# circuitPendulum4TIA00.net
KiCad netlist of a schematic drawn in EAGLE
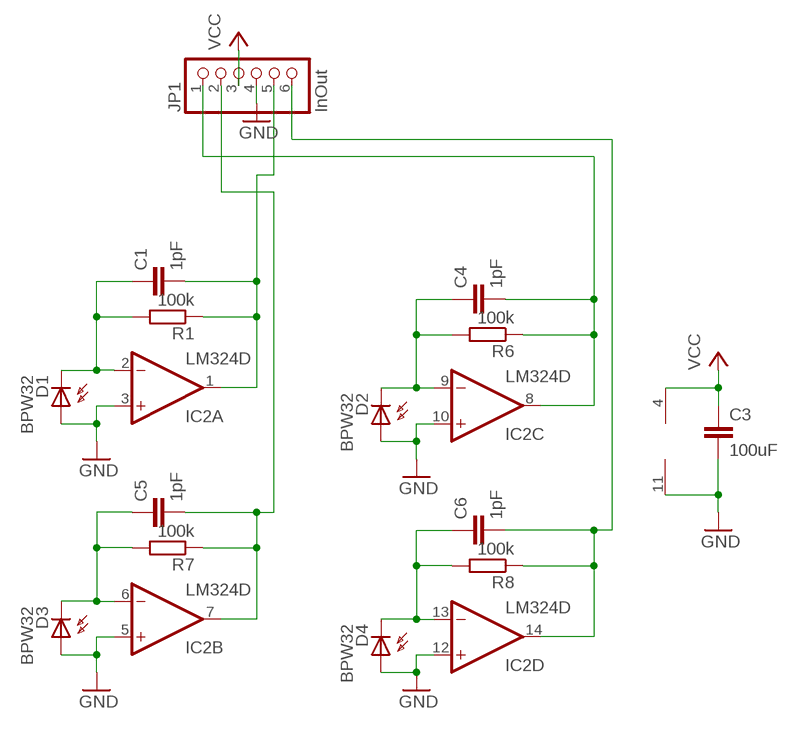
[diagram p0: schematic, sheet 1]

(export (version "E")
  (design (tool "Eeschema 10.0.6"))
  (components
    (comp (ref "C1")
      (value "1pF")
      (footprint "eagle-import:C0603")
      (libsource (lib "eagle-import") (part "C-EUC0603"))
    )
    (comp (ref "C3")
      (value "100uF")
      (footprint "eagle-import:C0603")
      (libsource (lib "eagle-import") (part "C-EUC0603"))
    )
    (comp (ref "C4")
      (value "1pF")
      (footprint "eagle-import:C0603")
      (libsource (lib "eagle-import") (part "C-EUC0603"))
    )
    (comp (ref "C5")
      (value "1pF")
      (footprint "eagle-import:C0603")
      (libsource (lib "eagle-import") (part "C-EUC0603"))
    )
    (comp (ref "C6")
      (value "1pF")
      (footprint "eagle-import:C0603")
      (libsource (lib "eagle-import") (part "C-EUC0603"))
    )
    (comp (ref "D1")
      (value "BPW32")
      (footprint "eagle-import:BPW32")
      (libsource (lib "eagle-import") (part "BPW32"))
    )
    (comp (ref "D2")
      (value "BPW32")
      (footprint "eagle-import:BPW32")
      (libsource (lib "eagle-import") (part "BPW32"))
    )
    (comp (ref "D3")
      (value "BPW32")
      (footprint "eagle-import:BPW32")
      (libsource (lib "eagle-import") (part "BPW32"))
    )
    (comp (ref "D4")
      (value "BPW32")
      (footprint "eagle-import:BPW32")
      (libsource (lib "eagle-import") (part "BPW32"))
    )
    (comp (ref "IC2")
      (value "LM324D")
      (footprint "eagle-import:SO14")
      (libsource (lib "eagle-import") (part "LM324D"))
    )
    (comp (ref "JP1")
      (value "InOut")
      (footprint "eagle-import:1X06M")
      (libsource (lib "eagle-import") (part "PINHD-1X6_2.00"))
    )
    (comp (ref "R1")
      (value "100k")
      (footprint "eagle-import:R0603")
      (libsource (lib "eagle-import") (part "R-EU_R0603"))
    )
    (comp (ref "R6")
      (value "100k")
      (footprint "eagle-import:R0603")
      (libsource (lib "eagle-import") (part "R-EU_R0603"))
    )
    (comp (ref "R7")
      (value "100k")
      (footprint "eagle-import:R0603")
      (libsource (lib "eagle-import") (part "R-EU_R0603"))
    )
    (comp (ref "R8")
      (value "100k")
      (footprint "eagle-import:R0603")
      (libsource (lib "eagle-import") (part "R-EU_R0603"))
    )
  )
  (nets
    (net (code "1") (name "GND") (class "Default")
      (node (ref "C3") (pin "2") (pinfunction "2_2") (pintype "passive"))
      (node (ref "D1") (pin "A") (pinfunction "A_A") (pintype "passive"))
      (node (ref "D2") (pin "A") (pinfunction "A_A") (pintype "passive"))
      (node (ref "D3") (pin "A") (pinfunction "A_A") (pintype "passive"))
      (node (ref "D4") (pin "A") (pinfunction "A_A") (pintype "passive"))
      (node (ref "IC2") (pin "10") (pinfunction "+IN_10") (pintype "input"))
      (node (ref "IC2") (pin "11") (pinfunction "V-_11") (pintype "power_in"))
      (node (ref "IC2") (pin "12") (pinfunction "+IN_12") (pintype "input"))
      (node (ref "IC2") (pin "3") (pinfunction "+IN_3") (pintype "input"))
      (node (ref "IC2") (pin "5") (pinfunction "+IN_5") (pintype "input"))
      (node (ref "JP1") (pin "4") (pinfunction "4_4") (pintype "passive"))
    )
    (net (code "2") (name "Net-(D1-C)") (class "Default")
      (node (ref "C1") (pin "1") (pinfunction "1_1") (pintype "passive"))
      (node (ref "D1") (pin "K") (pinfunction "C_K") (pintype "passive"))
      (node (ref "IC2") (pin "2") (pinfunction "-IN_2") (pintype "input"))
      (node (ref "R1") (pin "2") (pinfunction "2_2") (pintype "passive"))
    )
    (net (code "3") (name "Net-(D2-C)") (class "Default")
      (node (ref "C4") (pin "1") (pinfunction "1_1") (pintype "passive"))
      (node (ref "D2") (pin "K") (pinfunction "C_K") (pintype "passive"))
      (node (ref "IC2") (pin "9") (pinfunction "-IN_9") (pintype "input"))
      (node (ref "R6") (pin "2") (pinfunction "2_2") (pintype "passive"))
    )
    (net (code "4") (name "Net-(D3-C)") (class "Default")
      (node (ref "C5") (pin "1") (pinfunction "1_1") (pintype "passive"))
      (node (ref "D3") (pin "K") (pinfunction "C_K") (pintype "passive"))
      (node (ref "IC2") (pin "6") (pinfunction "-IN_6") (pintype "input"))
      (node (ref "R7") (pin "2") (pinfunction "2_2") (pintype "passive"))
    )
    (net (code "5") (name "Net-(D4-C)") (class "Default")
      (node (ref "C6") (pin "1") (pinfunction "1_1") (pintype "passive"))
      (node (ref "D4") (pin "K") (pinfunction "C_K") (pintype "passive"))
      (node (ref "IC2") (pin "13") (pinfunction "-IN_13") (pintype "input"))
      (node (ref "R8") (pin "2") (pinfunction "2_2") (pintype "passive"))
    )
    (net (code "6") (name "Net-(IC2A-OUT)") (class "Default")
      (node (ref "C1") (pin "2") (pinfunction "2_2") (pintype "passive"))
      (node (ref "IC2") (pin "1") (pinfunction "OUT_1") (pintype "output"))
      (node (ref "JP1") (pin "5") (pinfunction "5_5") (pintype "passive"))
      (node (ref "R1") (pin "1") (pinfunction "1_1") (pintype "passive"))
    )
    (net (code "7") (name "Net-(IC2B-OUT)") (class "Default")
      (node (ref "C5") (pin "2") (pinfunction "2_2") (pintype "passive"))
      (node (ref "IC2") (pin "7") (pinfunction "OUT_7") (pintype "output"))
      (node (ref "JP1") (pin "2") (pinfunction "2_2") (pintype "passive"))
      (node (ref "R7") (pin "1") (pinfunction "1_1") (pintype "passive"))
    )
    (net (code "8") (name "Net-(IC2C-OUT)") (class "Default")
      (node (ref "C4") (pin "2") (pinfunction "2_2") (pintype "passive"))
      (node (ref "IC2") (pin "8") (pinfunction "OUT_8") (pintype "output"))
      (node (ref "JP1") (pin "1") (pinfunction "1_1") (pintype "passive"))
      (node (ref "R6") (pin "1") (pinfunction "1_1") (pintype "passive"))
    )
    (net (code "9") (name "Net-(IC2D-OUT)") (class "Default")
      (node (ref "C6") (pin "2") (pinfunction "2_2") (pintype "passive"))
      (node (ref "IC2") (pin "14") (pinfunction "OUT_14") (pintype "output"))
      (node (ref "JP1") (pin "6") (pinfunction "6_6") (pintype "passive"))
      (node (ref "R8") (pin "1") (pinfunction "1_1") (pintype "passive"))
    )
    (net (code "10") (name "VCC") (class "Default")
      (node (ref "C3") (pin "1") (pinfunction "1_1") (pintype "passive"))
      (node (ref "IC2") (pin "4") (pinfunction "V+_4") (pintype "power_in"))
      (node (ref "JP1") (pin "3") (pinfunction "3_3") (pintype "passive"))
    )
  )
)
